# eNode_Spark.net
KiCad netlist of a schematic drawn in EAGLE
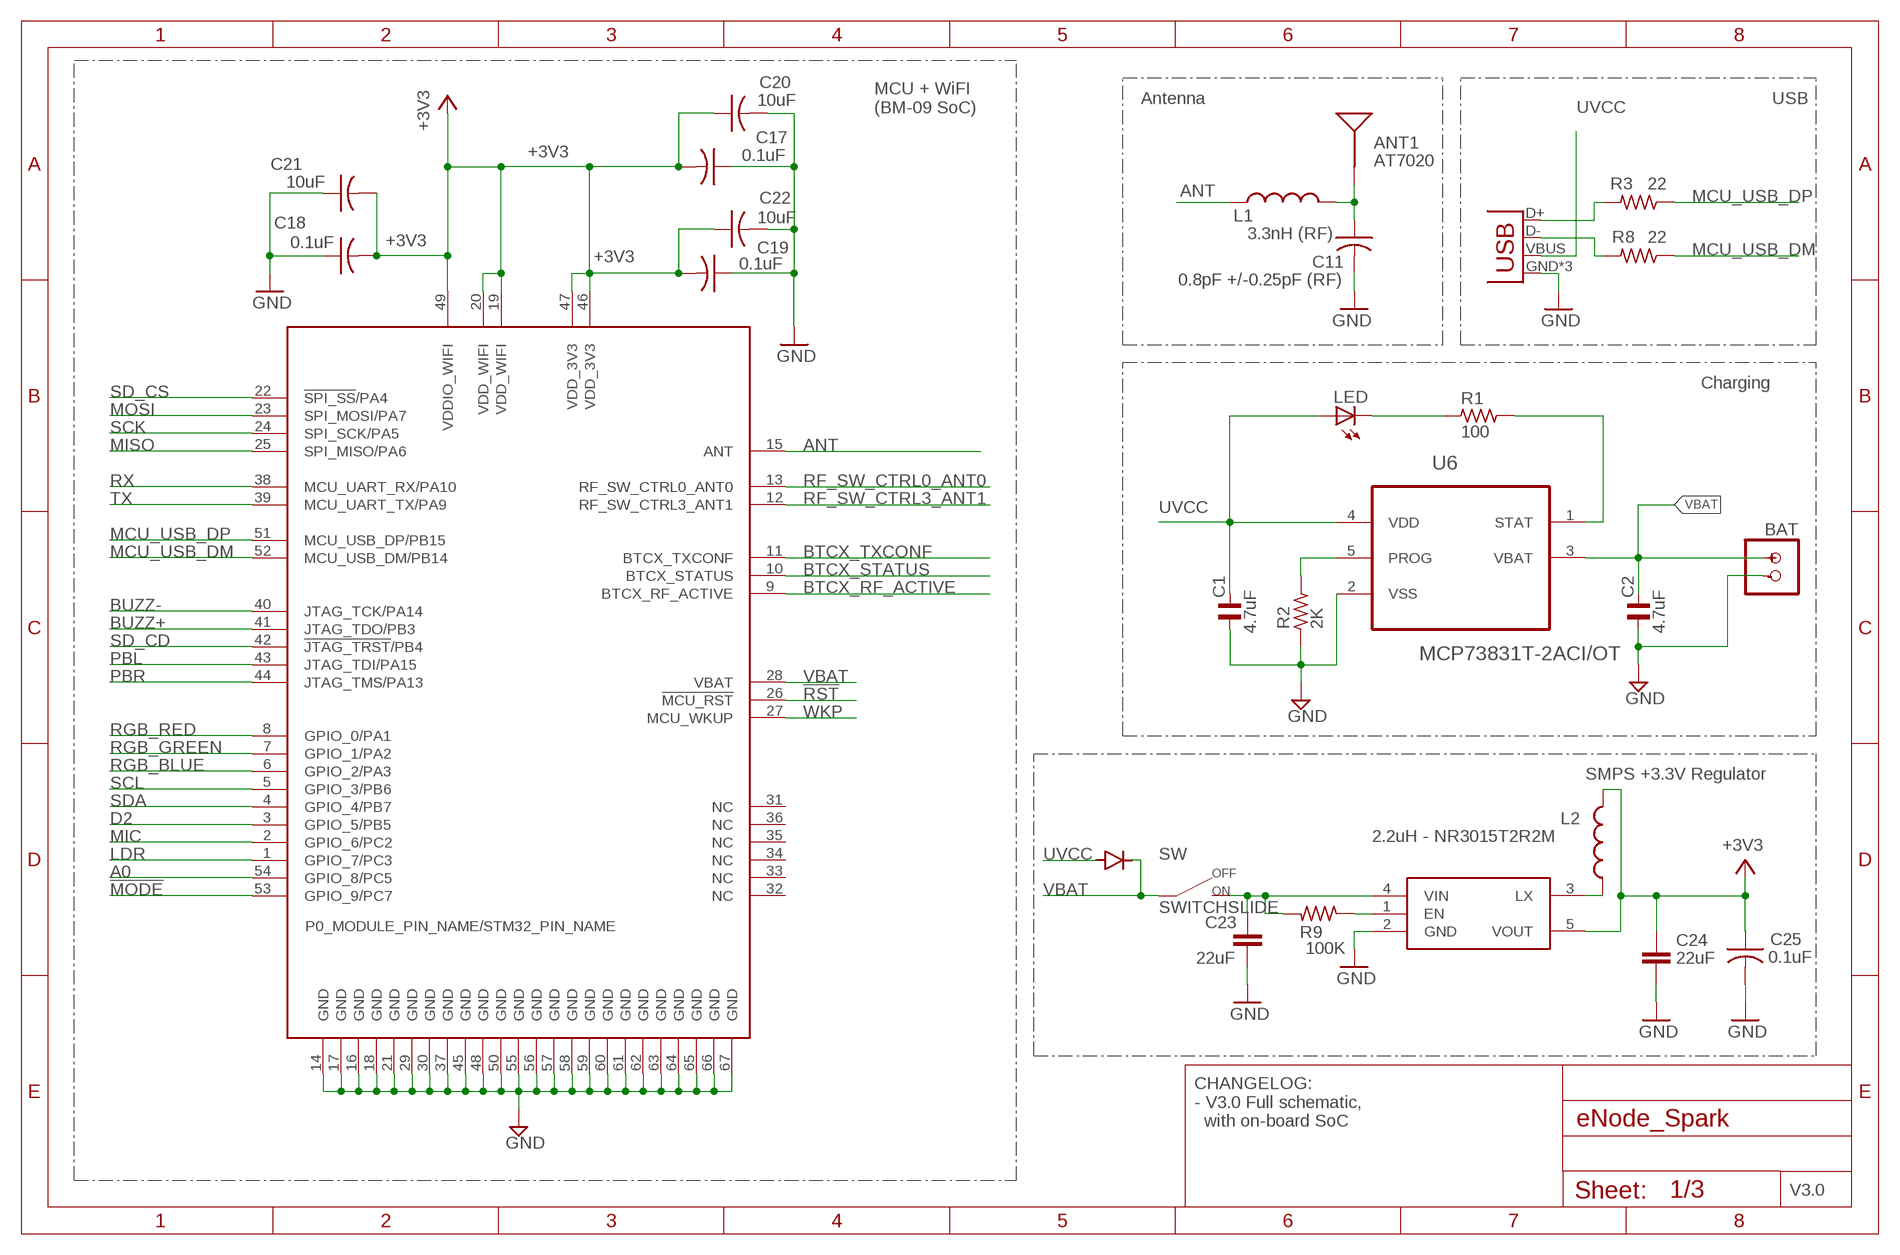
[diagram p0: schematic, sheet 1]
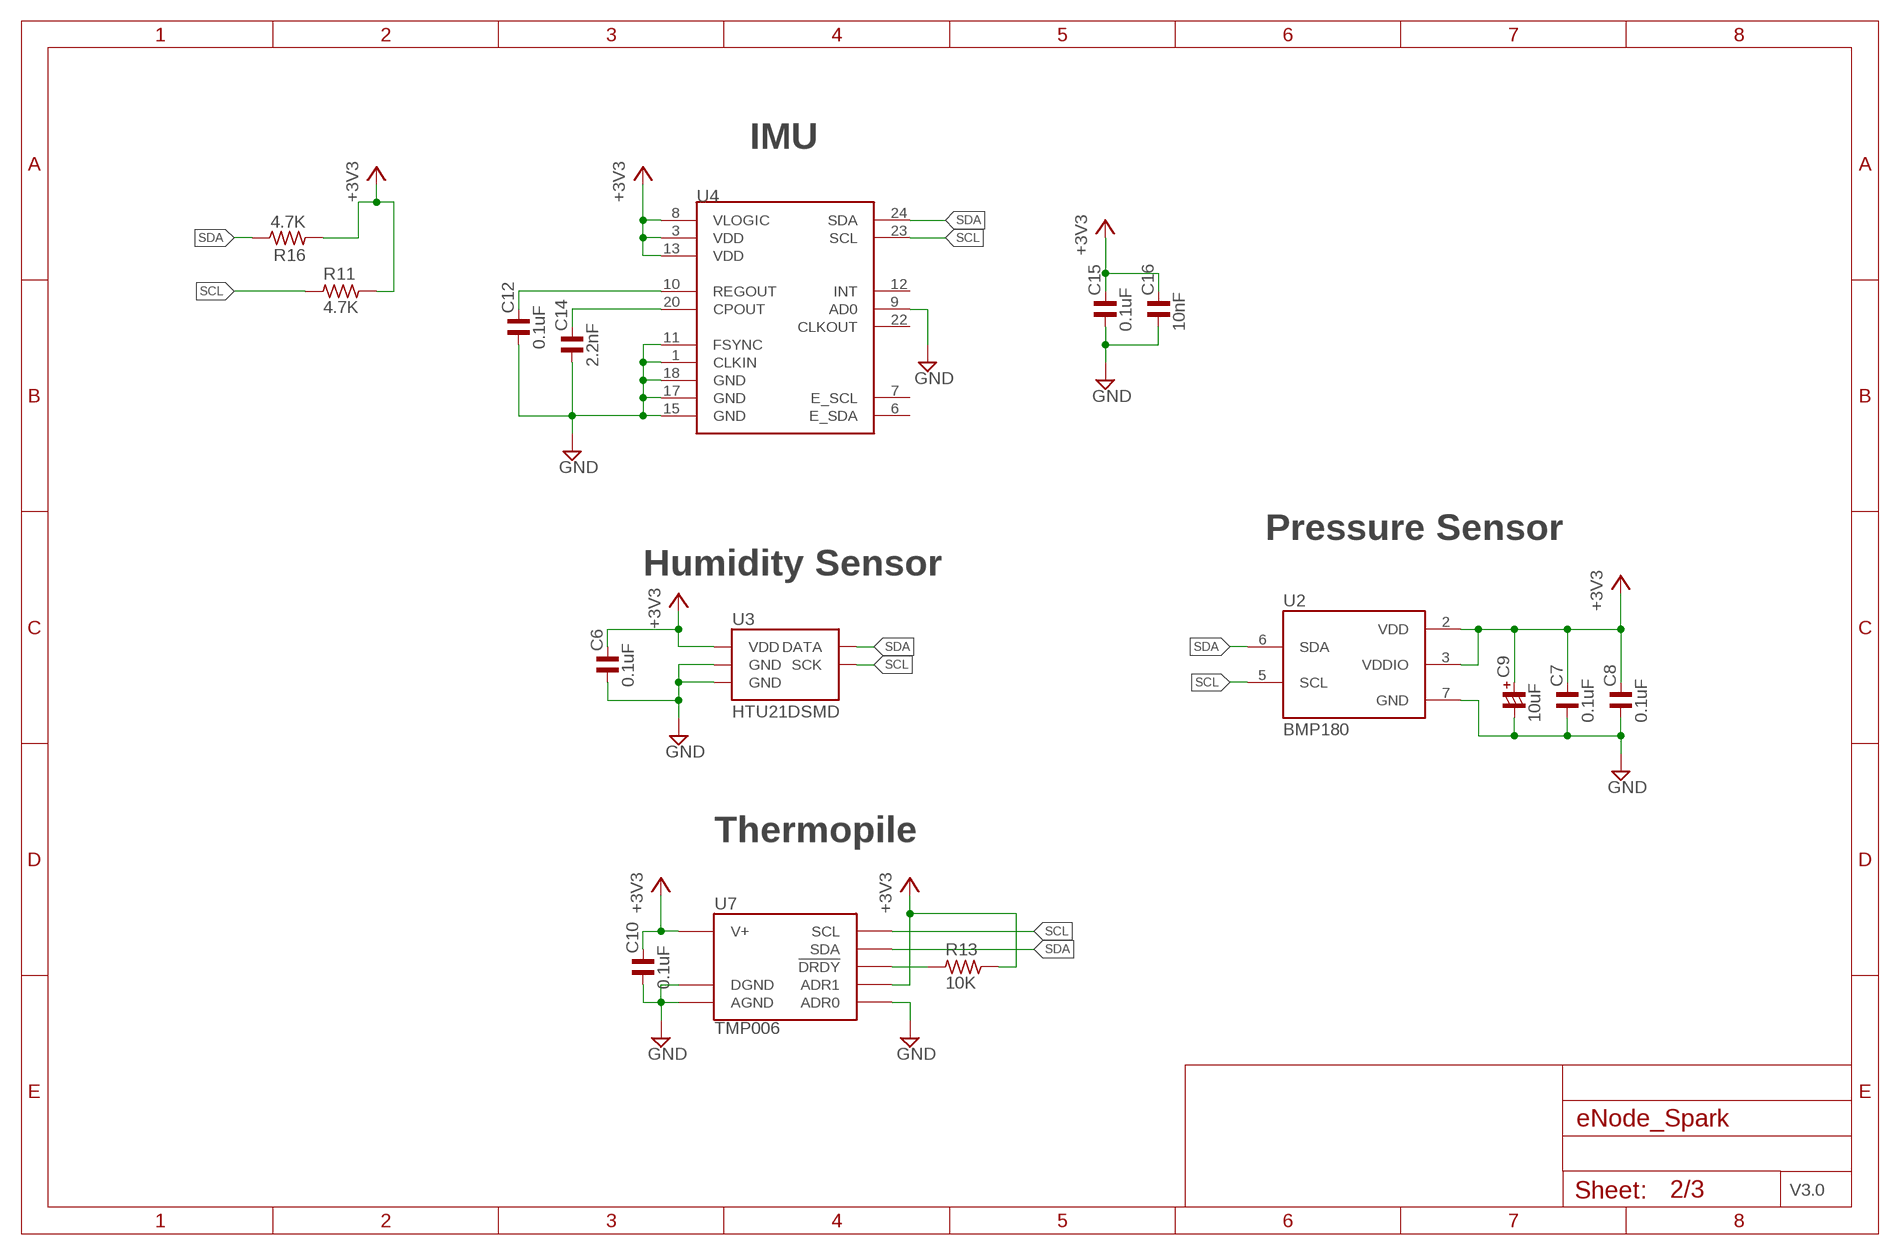
[diagram p1: schematic, sheet 2]
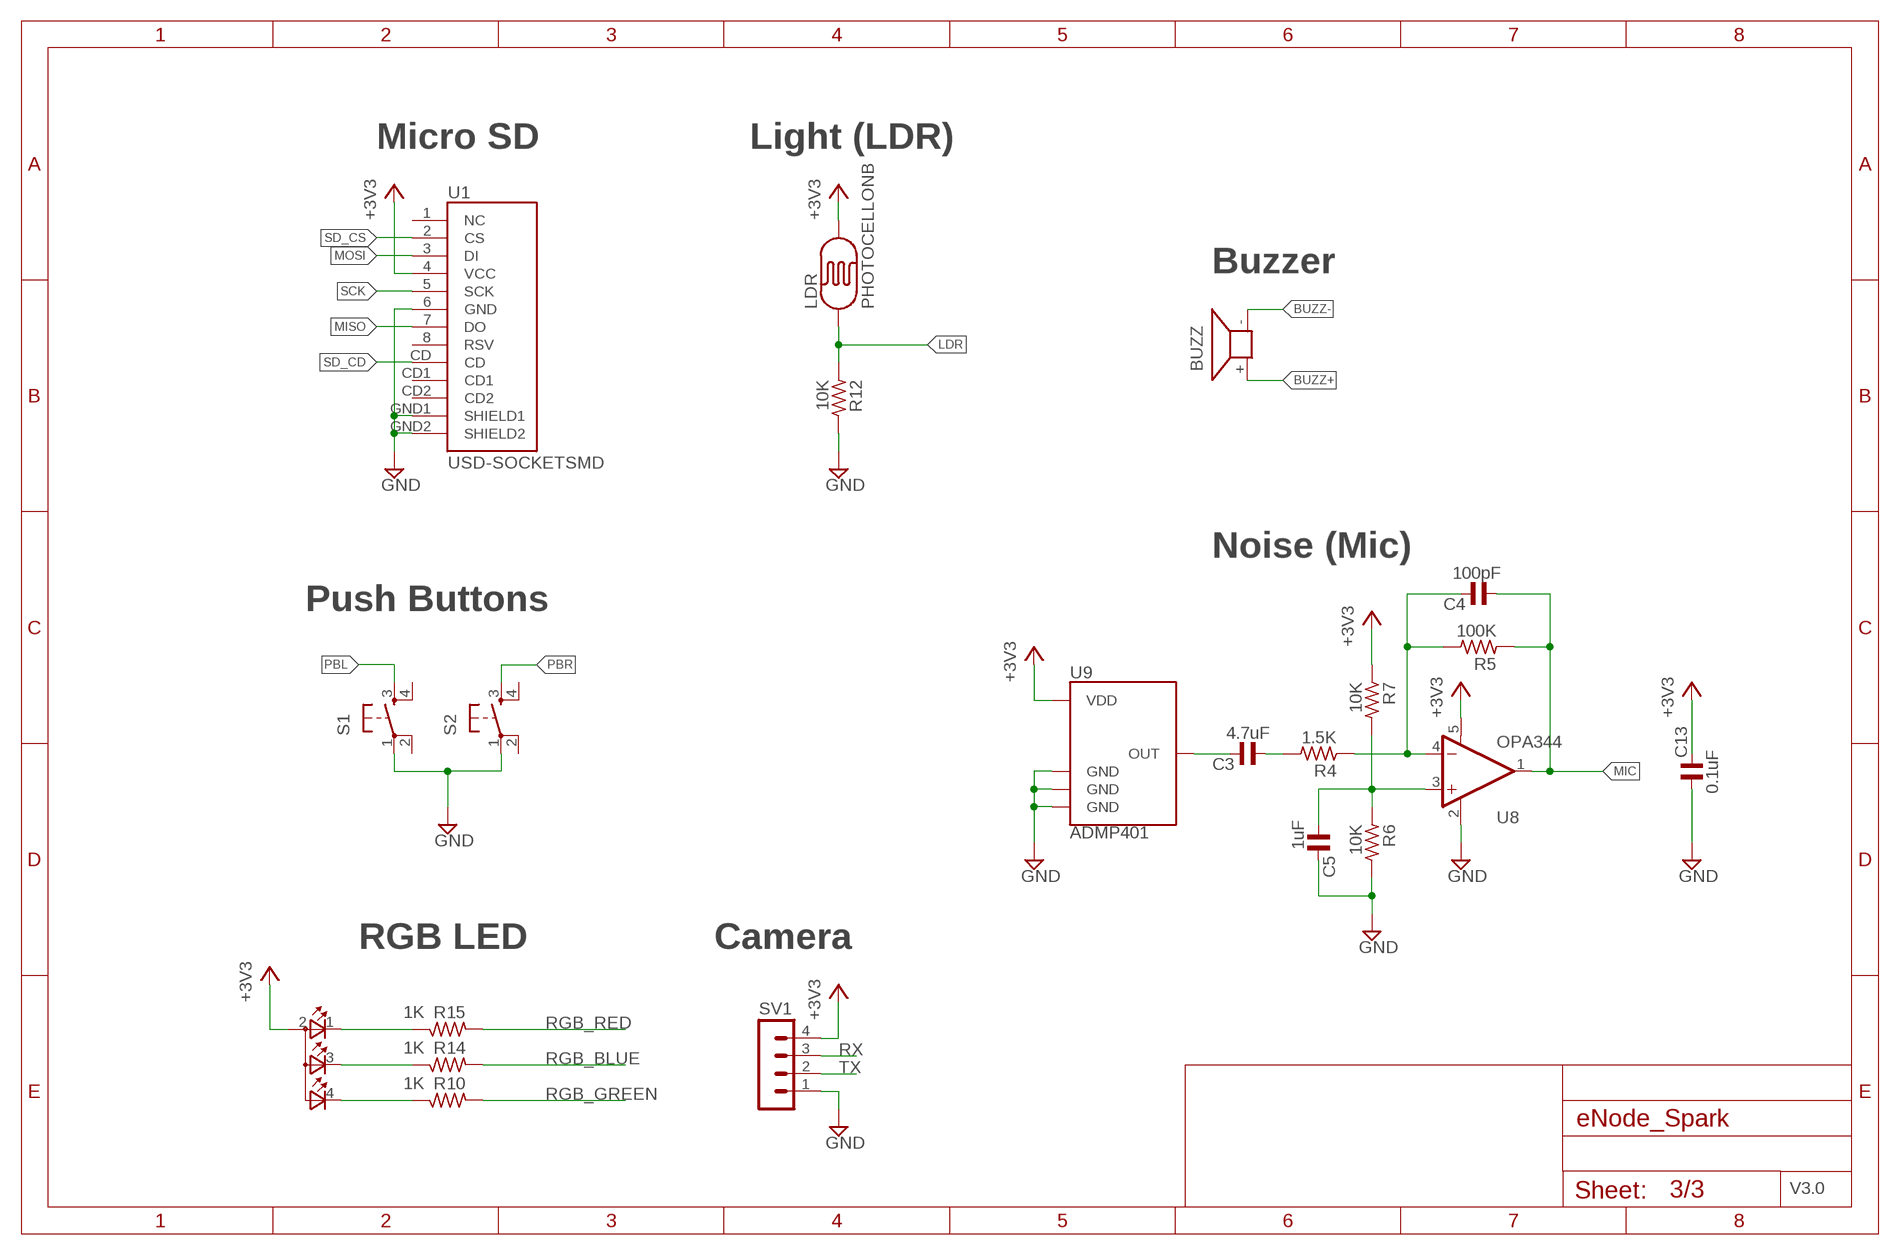
[diagram p2: schematic, sheet 3]

(export (version "E")
  (design (tool "Eeschema 10.0.6"))
  (components
    (comp (ref "C6")
      (value "0.1uF")
      (footprint "eagle-import:C0402")
      (libsource (lib "eagle-import") (part "C_0402"))
    )
    (comp (ref "C7")
      (value "0.1uF")
      (footprint "eagle-import:C0402")
      (libsource (lib "eagle-import") (part "C_0402"))
    )
    (comp (ref "C8")
      (value "0.1uF")
      (footprint "eagle-import:C0402")
      (libsource (lib "eagle-import") (part "C_0402"))
    )
    (comp (ref "C9")
      (value "10uF")
      (footprint "eagle-import:C1206_T")
      (libsource (lib "eagle-import") (part "CP_1206/T"))
    )
    (comp (ref "C10")
      (value "0.1uF")
      (footprint "eagle-import:C0402")
      (libsource (lib "eagle-import") (part "C_0402"))
    )
    (comp (ref "C12")
      (value "0.1uF")
      (footprint "eagle-import:C0402")
      (libsource (lib "eagle-import") (part "C_0402"))
    )
    (comp (ref "C14")
      (value "2.2nF")
      (footprint "eagle-import:C0402")
      (libsource (lib "eagle-import") (part "C_0402"))
    )
    (comp (ref "C15")
      (value "0.1uF")
      (footprint "eagle-import:C0402")
      (libsource (lib "eagle-import") (part "C_0402"))
    )
    (comp (ref "C16")
      (value "10nF")
      (footprint "eagle-import:C0402")
      (libsource (lib "eagle-import") (part "C_0402"))
    )
    (comp (ref "R11")
      (value "4.7K")
      (footprint "eagle-import:R0603")
      (libsource (lib "eagle-import") (part "R_0603"))
    )
    (comp (ref "R13")
      (value "10K")
      (footprint "eagle-import:R0603")
      (libsource (lib "eagle-import") (part "R_0603"))
    )
    (comp (ref "R16")
      (value "4.7K")
      (footprint "eagle-import:R0603")
      (libsource (lib "eagle-import") (part "R_0603"))
    )
    (comp (ref "U2")
      (value "BMP180")
      (footprint "eagle-import:BMP180")
      (libsource (lib "eagle-import") (part "BMP180"))
    )
    (comp (ref "U3")
      (value "HTU21DSMD")
      (footprint "eagle-import:HTU21D")
      (libsource (lib "eagle-import") (part "HTU21DSMD"))
    )
    (comp (ref "U4")
      (value "MPU-9150QFN-24-NP")
      (footprint "eagle-import:QFN-24-NP")
      (libsource (lib "eagle-import") (part "MPU-9150QFN-24-NP"))
    )
    (comp (ref "U7")
      (value "TMP006")
      (footprint "eagle-import:BGA8DS")
      (libsource (lib "eagle-import") (part "TMP006"))
    )
    (comp (ref "BUZZ")
      (value "BUZZER")
      (footprint "eagle-import:OFFBOARD_NOSIGN")
      (libsource (lib "eagle-import") (part "BUZZER"))
    )
    (comp (ref "C3")
      (value "4.7uF")
      (footprint "eagle-import:C0402")
      (libsource (lib "eagle-import") (part "C_0402"))
    )
    (comp (ref "C4")
      (value "100pF")
      (footprint "eagle-import:C0402")
      (libsource (lib "eagle-import") (part "C_0402"))
    )
    (comp (ref "C5")
      (value "1uF")
      (footprint "eagle-import:C0402")
      (libsource (lib "eagle-import") (part "C_0402"))
    )
    (comp (ref "C13")
      (value "0.1uF")
      (footprint "eagle-import:C0402")
      (libsource (lib "eagle-import") (part "C_0402"))
    )
    (comp (ref "LDR")
      (value "PHOTOCELLONB")
      (footprint "eagle-import:ON_BOARD")
      (libsource (lib "eagle-import") (part "PHOTOCELLONB"))
    )
    (comp (ref "LED2")
      (value "CREE_CLVBA-FKA")
      (footprint "eagle-import:P-LCC-4-3")
      (libsource (lib "eagle-import") (part "TOPLED-3PLCC"))
    )
    (comp (ref "R4")
      (value "1.5K")
      (footprint "eagle-import:R0402")
      (libsource (lib "eagle-import") (part "R_0402"))
    )
    (comp (ref "R5")
      (value "100K")
      (footprint "eagle-import:R0402")
      (libsource (lib "eagle-import") (part "R_0402"))
    )
    (comp (ref "R6")
      (value "10K")
      (footprint "eagle-import:R0402")
      (libsource (lib "eagle-import") (part "R_0402"))
    )
    (comp (ref "R7")
      (value "10K")
      (footprint "eagle-import:R0402")
      (libsource (lib "eagle-import") (part "R_0402"))
    )
    (comp (ref "R10")
      (value "1K")
      (footprint "eagle-import:R0402_B")
      (libsource (lib "eagle-import") (part "R-US_"))
    )
    (comp (ref "R12")
      (value "10K")
      (footprint "eagle-import:R0603")
      (libsource (lib "eagle-import") (part "R_0603"))
    )
    (comp (ref "R14")
      (value "1K")
      (footprint "eagle-import:R0402_B")
      (libsource (lib "eagle-import") (part "R-US_"))
    )
    (comp (ref "R15")
      (value "1K")
      (footprint "eagle-import:R0402_B")
      (libsource (lib "eagle-import") (part "R-US_"))
    )
    (comp (ref "S1")
      (value "TAC_SWITCHSMD")
      (footprint "eagle-import:TACTILE_SWITCH_SMD")
      (libsource (lib "eagle-import") (part "TAC_SWITCHSMD"))
    )
    (comp (ref "S2")
      (value "TAC_SWITCHSMD")
      (footprint "eagle-import:TACTILE_SWITCH_SMD")
      (libsource (lib "eagle-import") (part "TAC_SWITCHSMD"))
    )
    (comp (ref "SV1")
      (value "MA04-1")
      (footprint "eagle-import:MA04-1")
      (libsource (lib "eagle-import") (part "MA04-1"))
    )
    (comp (ref "U1")
      (value "USD-SOCKETSMD")
      (footprint "eagle-import:MICRO-SD-SOCKET-PP")
      (libsource (lib "eagle-import") (part "USD-SOCKETSMD"))
    )
    (comp (ref "U8")
      (value "OPA344")
      (footprint "eagle-import:SOT23-5")
      (libsource (lib "eagle-import") (part "OPA344"))
    )
    (comp (ref "U9")
      (value "ADMP401")
      (footprint "eagle-import:ADMP401")
      (libsource (lib "eagle-import") (part "ADMP401"))
    )
    (comp (ref "ANT1")
      (value "AT7020")
      (footprint "eagle-import:AT7020")
      (libsource (lib "eagle-import") (part "AT7020"))
    )
    (comp (ref "BAT")
      (value "BATTERYSMT")
      (footprint "eagle-import:JST-2-SMD")
      (libsource (lib "eagle-import") (part "BATTERYSMT"))
    )
    (comp (ref "C1")
      (value "4.7uF")
      (footprint "eagle-import:C0402")
      (libsource (lib "eagle-import") (part "C_0402"))
    )
    (comp (ref "C2")
      (value "4.7uF")
      (footprint "eagle-import:C0402")
      (libsource (lib "eagle-import") (part "C_0402"))
    )
    (comp (ref "C11")
      (value "0.8pF +/-0.25pF (RF)")
      (footprint "eagle-import:C0402_B")
      (libsource (lib "eagle-import") (part "C-US"))
    )
    (comp (ref "C17")
      (value "0.1uF")
      (footprint "eagle-import:C0402_B")
      (libsource (lib "eagle-import") (part "C-US"))
    )
    (comp (ref "C18")
      (value "0.1uF")
      (footprint "eagle-import:C0402_B")
      (libsource (lib "eagle-import") (part "C-US"))
    )
    (comp (ref "C19")
      (value "0.1uF")
      (footprint "eagle-import:C0402_B")
      (libsource (lib "eagle-import") (part "C-US"))
    )
    (comp (ref "C20")
      (value "10uF")
      (footprint "eagle-import:C0402_B")
      (libsource (lib "eagle-import") (part "C-US"))
    )
    (comp (ref "C21")
      (value "10uF")
      (footprint "eagle-import:C0402_B")
      (libsource (lib "eagle-import") (part "C-US"))
    )
    (comp (ref "C22")
      (value "10uF")
      (footprint "eagle-import:C0402_B")
      (libsource (lib "eagle-import") (part "C-US"))
    )
    (comp (ref "C23")
      (value "22uF")
      (footprint "eagle-import:C0603")
      (libsource (lib "eagle-import") (part "C-EUC0603"))
    )
    (comp (ref "C24")
      (value "22uF")
      (footprint "eagle-import:C0603")
      (libsource (lib "eagle-import") (part "C-EUC0603"))
    )
    (comp (ref "C25")
      (value "0.1uF")
      (footprint "eagle-import:C0402")
      (libsource (lib "eagle-import") (part "C-USC0402"))
    )
    (comp (ref "D1")
      (value "DIODE")
      (footprint "eagle-import:DIODE-DO-220AA(SMP)")
      (libsource (lib "eagle-import") (part "DIODE"))
    )
    (comp (ref "L1")
      (value "3.3nH (RF)")
      (footprint "eagle-import:L0402_B")
      (libsource (lib "eagle-import") (part "INDUCTOR"))
    )
    (comp (ref "L2")
      (value "2.2uH - NR3015T2R2M")
      (footprint "eagle-import:INDUCTOR-NR3015")
      (libsource (lib "eagle-import") (part "INDUCTORB"))
    )
    (comp (ref "LED")
      (value "LED")
      (footprint "eagle-import:RA_SMD_LED")
      (libsource (lib "eagle-import") (part "LED"))
    )
    (comp (ref "R1")
      (value "100")
      (footprint "eagle-import:R0603")
      (libsource (lib "eagle-import") (part "R_0603"))
    )
    (comp (ref "R2")
      (value "2K")
      (footprint "eagle-import:R0603")
      (libsource (lib "eagle-import") (part "R_0603"))
    )
    (comp (ref "R3")
      (value "22")
      (footprint "eagle-import:R0402_B")
      (libsource (lib "eagle-import") (part "R-US_"))
    )
    (comp (ref "R8")
      (value "22")
      (footprint "eagle-import:R0402_B")
      (libsource (lib "eagle-import") (part "R-US_"))
    )
    (comp (ref "R9")
      (value "100K")
      (footprint "eagle-import:R0402_B")
      (libsource (lib "eagle-import") (part "R-US_"))
    )
    (comp (ref "SW")
      (value "SWITCHSLIDE")
      (footprint "eagle-import:CHANGE_OVER_SLIDE")
      (libsource (lib "eagle-import") (part "SWITCHSLIDE"))
    )
    (comp (ref "U$7")
      (value "R8008-33")
      (footprint "eagle-import:SOT23-5")
      (libsource (lib "eagle-import") (part "R8008-33"))
    )
    (comp (ref "U6")
      (value "MCP73831T-2ACI/OT")
      (footprint "eagle-import:SOT95P280X145-5N")
      (libsource (lib "eagle-import") (part "MCP73831T-2ACI/OT"))
    )
    (comp (ref "U10")
      (value "WM-N-BM-09")
      (footprint "eagle-import:WM-N-BM-09")
      (libsource (lib "eagle-import") (part "WM-N-BM-09"))
    )
    (comp (ref "X1")
      (value "USB-MICROB")
      (footprint "eagle-import:USB-MICROB-SLOT-HOLE")
      (libsource (lib "eagle-import") (part "USBUSB-MICROB-SLOT-HOLE"))
    )
  )
  (nets
    (net (code "1") (name "+3V3") (class "Default")
      (node (ref "C10") (pin "2") (pinfunction "2_2") (pintype "passive"))
      (node (ref "C13") (pin "2") (pinfunction "2_2") (pintype "passive"))
      (node (ref "C15") (pin "2") (pinfunction "2_2") (pintype "passive"))
      (node (ref "C16") (pin "2") (pinfunction "2_2") (pintype "passive"))
      (node (ref "C17") (pin "2") (pinfunction "2_2") (pintype "passive"))
      (node (ref "C18") (pin "2") (pinfunction "2_2") (pintype "passive"))
      (node (ref "C19") (pin "2") (pinfunction "2_2") (pintype "passive"))
      (node (ref "C20") (pin "1") (pinfunction "1_1") (pintype "passive"))
      (node (ref "C21") (pin "2") (pinfunction "2_2") (pintype "passive"))
      (node (ref "C22") (pin "1") (pinfunction "1_1") (pintype "passive"))
      (node (ref "C24") (pin "1") (pinfunction "1_1") (pintype "passive"))
      (node (ref "C25") (pin "1") (pinfunction "1_1") (pintype "passive"))
      (node (ref "C6") (pin "2") (pinfunction "2_2") (pintype "passive"))
      (node (ref "C7") (pin "2") (pinfunction "2_2") (pintype "passive"))
      (node (ref "C8") (pin "2") (pinfunction "2_2") (pintype "passive"))
      (node (ref "C9") (pin "+") (pinfunction "+_+") (pintype "passive"))
      (node (ref "L2") (pin "2") (pinfunction "2_2") (pintype "passive"))
      (node (ref "LDR") (pin "2") (pinfunction "P$2_2") (pintype "bidirectional"))
      (node (ref "LED2") (pin "2") (pinfunction "A2_2") (pintype "passive"))
      (node (ref "R11") (pin "2") (pinfunction "2_2") (pintype "passive"))
      (node (ref "R13") (pin "2") (pinfunction "2_2") (pintype "passive"))
      (node (ref "R16") (pin "1") (pinfunction "1_1") (pintype "passive"))
      (node (ref "R7") (pin "1") (pinfunction "1_1") (pintype "passive"))
      (node (ref "SV1") (pin "4") (pinfunction "4_4") (pintype "passive"))
      (node (ref "U$7") (pin "5") (pinfunction "VOUT_5") (pintype "bidirectional"))
      (node (ref "U1") (pin "4") (pinfunction "VCC_4") (pintype "bidirectional"))
      (node (ref "U10") (pin "19") (pinfunction "VDD_WIFI_19") (pintype "bidirectional"))
      (node (ref "U10") (pin "20") (pinfunction "VDD_WIFI_20") (pintype "bidirectional"))
      (node (ref "U10") (pin "46") (pinfunction "VDD_3V3_46") (pintype "bidirectional"))
      (node (ref "U10") (pin "47") (pinfunction "VDD_3V3_47") (pintype "bidirectional"))
      (node (ref "U10") (pin "49") (pinfunction "VDDIO_WIFI_49") (pintype "bidirectional"))
      (node (ref "U2") (pin "2") (pinfunction "VDD_2") (pintype "power_in"))
      (node (ref "U2") (pin "3") (pinfunction "VDDIO_3") (pintype "power_in"))
      (node (ref "U3") (pin "VDD") (pinfunction "VDD_VDD") (pintype "power_in"))
      (node (ref "U4") (pin "13") (pinfunction "VDD_13") (pintype "bidirectional"))
      (node (ref "U4") (pin "3") (pinfunction "VDD_3") (pintype "bidirectional"))
      (node (ref "U4") (pin "8") (pinfunction "VLOGIC_8") (pintype "bidirectional"))
      (node (ref "U7") (pin "A3") (pinfunction "V+_A3") (pintype "bidirectional"))
      (node (ref "U7") (pin "B1") (pinfunction "ADR1_B1") (pintype "bidirectional"))
      (node (ref "U8") (pin "5") (pinfunction "V+_5") (pintype "power_in"))
      (node (ref "U9") (pin "5") (pinfunction "VDD_5") (pintype "bidirectional"))
    )
    (net (code "2") (name "A0") (class "Default")
      (node (ref "U10") (pin "54") (pinfunction "GPIO_8/PC5_54") (pintype "bidirectional"))
    )
    (net (code "3") (name "ANT") (class "Default")
      (node (ref "L1") (pin "1") (pinfunction "1_1") (pintype "passive"))
      (node (ref "U10") (pin "15") (pinfunction "ANT_15") (pintype "bidirectional"))
    )
    (net (code "4") (name "BTCX_RF_ACTIVE") (class "Default")
      (node (ref "U10") (pin "9") (pinfunction "BTCX_RF_ACTIVE_9") (pintype "bidirectional"))
    )
    (net (code "5") (name "BTCX_STATUS") (class "Default")
      (node (ref "U10") (pin "10") (pinfunction "BTCX_STATUS_10") (pintype "bidirectional"))
    )
    (net (code "6") (name "BTCX_TXCONF") (class "Default")
      (node (ref "U10") (pin "11") (pinfunction "BTCX_TXCONF_11") (pintype "bidirectional"))
    )
    (net (code "7") (name "BUZZ+") (class "Default")
      (node (ref "BUZZ") (pin "+") (pinfunction "+_+") (pintype "passive"))
      (node (ref "U10") (pin "41") (pinfunction "JTAG_TDO/PB3_41") (pintype "bidirectional"))
    )
    (net (code "8") (name "BUZZ-") (class "Default")
      (node (ref "BUZZ") (pin "-") (pinfunction "-_-") (pintype "passive"))
      (node (ref "U10") (pin "40") (pinfunction "JTAG_TCK/PA14_40") (pintype "bidirectional"))
    )
    (net (code "9") (name "D2") (class "Default")
      (node (ref "U10") (pin "3") (pinfunction "GPIO_5/PB5_3") (pintype "bidirectional"))
    )
    (net (code "10") (name "GND") (class "Default")
      (node (ref "BAT") (pin "-") (pinfunction "-_-") (pintype "passive"))
      (node (ref "C1") (pin "1") (pinfunction "1_1") (pintype "passive"))
      (node (ref "C10") (pin "1") (pinfunction "1_1") (pintype "passive"))
      (node (ref "C11") (pin "2") (pinfunction "2_2") (pintype "passive"))
      (node (ref "C12") (pin "1") (pinfunction "1_1") (pintype "passive"))
      (node (ref "C13") (pin "1") (pinfunction "1_1") (pintype "passive"))
      (node (ref "C14") (pin "1") (pinfunction "1_1") (pintype "passive"))
      (node (ref "C15") (pin "1") (pinfunction "1_1") (pintype "passive"))
      (node (ref "C16") (pin "1") (pinfunction "1_1") (pintype "passive"))
      (node (ref "C17") (pin "1") (pinfunction "1_1") (pintype "passive"))
      (node (ref "C18") (pin "1") (pinfunction "1_1") (pintype "passive"))
      (node (ref "C19") (pin "1") (pinfunction "1_1") (pintype "passive"))
      (node (ref "C2") (pin "1") (pinfunction "1_1") (pintype "passive"))
      (node (ref "C20") (pin "2") (pinfunction "2_2") (pintype "passive"))
      (node (ref "C21") (pin "1") (pinfunction "1_1") (pintype "passive"))
      (node (ref "C22") (pin "2") (pinfunction "2_2") (pintype "passive"))
      (node (ref "C23") (pin "2") (pinfunction "2_2") (pintype "passive"))
      (node (ref "C24") (pin "2") (pinfunction "2_2") (pintype "passive"))
      (node (ref "C25") (pin "2") (pinfunction "2_2") (pintype "passive"))
      (node (ref "C5") (pin "2") (pinfunction "2_2") (pintype "passive"))
      (node (ref "C6") (pin "1") (pinfunction "1_1") (pintype "passive"))
      (node (ref "C7") (pin "1") (pinfunction "1_1") (pintype "passive"))
      (node (ref "C8") (pin "1") (pinfunction "1_1") (pintype "passive"))
      (node (ref "C9") (pin "-") (pinfunction "-_-") (pintype "passive"))
      (node (ref "R12") (pin "2") (pinfunction "2_2") (pintype "passive"))
      (node (ref "R2") (pin "1") (pinfunction "1_1") (pintype "passive"))
      (node (ref "R6") (pin "2") (pinfunction "2_2") (pintype "passive"))
      (node (ref "S1") (pin "1") (pinfunction "1_1") (pintype "passive"))
      (node (ref "S2") (pin "1") (pinfunction "1_1") (pintype "passive"))
      (node (ref "SV1") (pin "1") (pinfunction "1_1") (pintype "passive"))
      (node (ref "U$7") (pin "2") (pinfunction "GND_2") (pintype "bidirectional"))
      (node (ref "U1") (pin "6") (pinfunction "GND_6") (pintype "bidirectional"))
      (node (ref "U1") (pin "GND1") (pinfunction "SHIELD1_GND1") (pintype "bidirectional"))
      (node (ref "U1") (pin "GND2") (pinfunction "SHIELD2_GND2") (pintype "bidirectional"))
      (node (ref "U10") (pin "14") (pinfunction "GND_14") (pintype "bidirectional"))
      (node (ref "U10") (pin "16") (pinfunction "GND_16") (pintype "bidirectional"))
      (node (ref "U10") (pin "17") (pinfunction "GND_17") (pintype "bidirectional"))
      (node (ref "U10") (pin "18") (pinfunction "GND_18") (pintype "bidirectional"))
      (node (ref "U10") (pin "21") (pinfunction "GND_21") (pintype "bidirectional"))
      (node (ref "U10") (pin "29") (pinfunction "GND_29") (pintype "bidirectional"))
      (node (ref "U10") (pin "30") (pinfunction "GND_30") (pintype "bidirectional"))
      (node (ref "U10") (pin "37") (pinfunction "GND_37") (pintype "bidirectional"))
      (node (ref "U10") (pin "45") (pinfunction "GND_45") (pintype "bidirectional"))
      (node (ref "U10") (pin "48") (pinfunction "GND_48") (pintype "bidirectional"))
      (node (ref "U10") (pin "50") (pinfunction "GND_50") (pintype "bidirectional"))
      (node (ref "U10") (pin "55") (pinfunction "GND_55") (pintype "bidirectional"))
      (node (ref "U10") (pin "56") (pinfunction "GND_56") (pintype "bidirectional"))
      (node (ref "U10") (pin "57") (pinfunction "GND_57") (pintype "bidirectional"))
      (node (ref "U10") (pin "58") (pinfunction "GND_58") (pintype "bidirectional"))
      (node (ref "U10") (pin "59") (pinfunction "GND_59") (pintype "bidirectional"))
      (node (ref "U10") (pin "60") (pinfunction "GND_60") (pintype "bidirectional"))
      (node (ref "U10") (pin "61") (pinfunction "GND_61") (pintype "bidirectional"))
      (node (ref "U10") (pin "62") (pinfunction "GND_62") (pintype "bidirectional"))
      (node (ref "U10") (pin "63") (pinfunction "GND_63") (pintype "bidirectional"))
      (node (ref "U10") (pin "64") (pinfunction "GND_64") (pintype "bidirectional"))
      (node (ref "U10") (pin "65") (pinfunction "GND_65") (pintype "bidirectional"))
      (node (ref "U10") (pin "66") (pinfunction "GND_66") (pintype "bidirectional"))
      (node (ref "U10") (pin "67") (pinfunction "GND_67") (pintype "bidirectional"))
      (node (ref "U2") (pin "7") (pinfunction "GND_7") (pintype "power_in"))
      (node (ref "U3") (pin "7") (pinfunction "GND_7") (pintype "power_in"))
      (node (ref "U3") (pin "GND") (pinfunction "GND_GND") (pintype "power_in"))
      (node (ref "U4") (pin "1") (pinfunction "CLKIN_1") (pintype "bidirectional"))
      (node (ref "U4") (pin "11") (pinfunction "FSYNC_11") (pintype "bidirectional"))
      (node (ref "U4") (pin "15") (pinfunction "GND_15") (pintype "bidirectional"))
      (node (ref "U4") (pin "17") (pinfunction "GND_17") (pintype "bidirectional"))
      (node (ref "U4") (pin "18") (pinfunction "GND_18") (pintype "bidirectional"))
      (node (ref "U4") (pin "9") (pinfunction "AD0_9") (pintype "bidirectional"))
      (node (ref "U6") (pin "2") (pinfunction "VSS_2") (pintype "power_in"))
      (node (ref "U7") (pin "A1") (pinfunction "DGND_A1") (pintype "bidirectional"))
      (node (ref "U7") (pin "A2") (pinfunction "AGND_A2") (pintype "bidirectional"))
      (node (ref "U7") (pin "C1") (pinfunction "ADR0_C1") (pintype "bidirectional"))
      (node (ref "U8") (pin "2") (pinfunction "V-_2") (pintype "power_in"))
      (node (ref "U9") (pin "2") (pinfunction "GND_2") (pintype "bidirectional"))
      (node (ref "U9") (pin "4") (pinfunction "GND_4") (pintype "bidirectional"))
      (node (ref "U9") (pin "6") (pinfunction "GND_6") (pintype "bidirectional"))
      (node (ref "X1") (pin "GND") (pinfunction "GND_GND") (pintype "bidirectional"))
      (node (ref "X1") (pin "MT1") (pinfunction "GND_MT1") (pintype "bidirectional"))
      (node (ref "X1") (pin "MT2") (pinfunction "GND_MT2") (pintype "bidirectional"))
    )
    (net (code "11") (name "LDR") (class "Default")
      (node (ref "LDR") (pin "1") (pinfunction "P$1_1") (pintype "bidirectional"))
      (node (ref "R12") (pin "1") (pinfunction "1_1") (pintype "passive"))
      (node (ref "U10") (pin "1") (pinfunction "GPIO_7/PC3_1") (pintype "bidirectional"))
    )
    (net (code "12") (name "MCU_USB_DM") (class "Default")
      (node (ref "R8") (pin "1") (pinfunction "1_1") (pintype "passive"))
      (node (ref "U10") (pin "52") (pinfunction "MCU_USB_DM/PB14_52") (pintype "bidirectional"))
    )
    (net (code "13") (name "MCU_USB_DP") (class "Default")
      (node (ref "R3") (pin "1") (pinfunction "1_1") (pintype "passive"))
      (node (ref "U10") (pin "51") (pinfunction "MCU_USB_DP/PB15_51") (pintype "bidirectional"))
    )
    (net (code "14") (name "MIC") (class "Default")
      (node (ref "C4") (pin "1") (pinfunction "1_1") (pintype "passive"))
      (node (ref "R5") (pin "1") (pinfunction "1_1") (pintype "passive"))
      (node (ref "U10") (pin "2") (pinfunction "GPIO_6/PC2_2") (pintype "bidirectional"))
      (node (ref "U8") (pin "1") (pinfunction "OUT_1") (pintype "output"))
    )
    (net (code "15") (name "MISO") (class "Default")
      (node (ref "U1") (pin "7") (pinfunction "DO_7") (pintype "bidirectional"))
      (node (ref "U10") (pin "25") (pinfunction "SPI_MISO/PA6_25") (pintype "bidirectional"))
    )
    (net (code "16") (name "MOSI") (class "Default")
      (node (ref "U1") (pin "3") (pinfunction "DI_3") (pintype "bidirectional"))
      (node (ref "U10") (pin "23") (pinfunction "SPI_MOSI/PA7_23") (pintype "bidirectional"))
    )
    (net (code "17") (name "Net-(ANT1-SIGNAL)") (class "Default")
      (node (ref "ANT1") (pin "1") (pinfunction "SIGNAL_1") (pintype "bidirectional"))
      (node (ref "C11") (pin "1") (pinfunction "1_1") (pintype "passive"))
      (node (ref "L1") (pin "2") (pinfunction "2_2") (pintype "passive"))
    )
    (net (code "18") (name "Net-(C3-Pad1)") (class "Default")
      (node (ref "C3") (pin "1") (pinfunction "1_1") (pintype "passive"))
      (node (ref "R4") (pin "2") (pinfunction "2_2") (pintype "passive"))
    )
    (net (code "19") (name "Net-(LED-PadC)") (class "Default")
      (node (ref "LED") (pin "C") (pinfunction "C_C") (pintype "passive"))
      (node (ref "R1") (pin "1") (pinfunction "1_1") (pintype "passive"))
    )
    (net (code "20") (name "Net-(LED2-CBLUE)") (class "Default")
      (node (ref "LED2") (pin "3") (pinfunction "CBLUE_3") (pintype "passive"))
      (node (ref "R14") (pin "1") (pinfunction "1_1") (pintype "passive"))
    )
    (net (code "21") (name "Net-(LED2-CGREEN)") (class "Default")
      (node (ref "LED2") (pin "4") (pinfunction "CGREEN_4") (pintype "passive"))
      (node (ref "R10") (pin "1") (pinfunction "1_1") (pintype "passive"))
    )
    (net (code "22") (name "Net-(LED2-CRED)") (class "Default")
      (node (ref "LED2") (pin "1") (pinfunction "CRED_1") (pintype "passive"))
      (node (ref "R15") (pin "1") (pinfunction "1_1") (pintype "passive"))
    )
    (net (code "23") (name "Net-(R3-Pad2)") (class "Default")
      (node (ref "R3") (pin "2") (pinfunction "2_2") (pintype "passive"))
      (node (ref "X1") (pin "D+") (pinfunction "D+_D+") (pintype "bidirectional"))
    )
    (net (code "24") (name "Net-(R8-Pad2)") (class "Default")
      (node (ref "R8") (pin "2") (pinfunction "2_2") (pintype "passive"))
      (node (ref "X1") (pin "D-") (pinfunction "D-_D-") (pintype "bidirectional"))
    )
    (net (code "25") (name "Net-(U$7-EN)") (class "Default")
      (node (ref "R9") (pin "1") (pinfunction "1_1") (pintype "passive"))
      (node (ref "U$7") (pin "1") (pinfunction "EN_1") (pintype "bidirectional"))
    )
    (net (code "26") (name "Net-(U$7-LX)") (class "Default")
      (node (ref "L2") (pin "1") (pinfunction "1_1") (pintype "passive"))
      (node (ref "U$7") (pin "3") (pinfunction "LX_3") (pintype "bidirectional"))
    )
    (net (code "27") (name "Net-(U4-CPOUT)") (class "Default")
      (node (ref "C14") (pin "2") (pinfunction "2_2") (pintype "passive"))
      (node (ref "U4") (pin "20") (pinfunction "CPOUT_20") (pintype "bidirectional"))
    )
    (net (code "28") (name "Net-(U4-REGOUT)") (class "Default")
      (node (ref "C12") (pin "2") (pinfunction "2_2") (pintype "passive"))
      (node (ref "U4") (pin "10") (pinfunction "REGOUT_10") (pintype "bidirectional"))
    )
    (net (code "29") (name "Net-(U6-PROG)") (class "Default")
      (node (ref "R2") (pin "2") (pinfunction "2_2") (pintype "passive"))
      (node (ref "U6") (pin "5") (pinfunction "PROG_5") (pintype "input"))
    )
    (net (code "30") (name "Net-(U6-STAT)") (class "Default")
      (node (ref "R1") (pin "2") (pinfunction "2_2") (pintype "passive"))
      (node (ref "U6") (pin "1") (pinfunction "STAT_1") (pintype "output"))
    )
    (net (code "31") (name "Net-(U7-~{DRDY})") (class "Default")
      (node (ref "R13") (pin "1") (pinfunction "1_1") (pintype "passive"))
      (node (ref "U7") (pin "C2") (pinfunction "~{DRDY}_C2") (pintype "bidirectional"))
    )
    (net (code "32") (name "Net-(U8-+IN)") (class "Default")
      (node (ref "C5") (pin "1") (pinfunction "1_1") (pintype "passive"))
      (node (ref "R6") (pin "1") (pinfunction "1_1") (pintype "passive"))
      (node (ref "R7") (pin "2") (pinfunction "2_2") (pintype "passive"))
      (node (ref "U8") (pin "3") (pinfunction "+IN_3") (pintype "input"))
    )
    (net (code "33") (name "Net-(U8--IN)") (class "Default")
      (node (ref "C4") (pin "2") (pinfunction "2_2") (pintype "passive"))
      (node (ref "R4") (pin "1") (pinfunction "1_1") (pintype "passive"))
      (node (ref "R5") (pin "2") (pinfunction "2_2") (pintype "passive"))
      (node (ref "U8") (pin "4") (pinfunction "-IN_4") (pintype "input"))
    )
    (net (code "34") (name "Net-(U9-OUT)") (class "Default")
      (node (ref "C3") (pin "2") (pinfunction "2_2") (pintype "passive"))
      (node (ref "U9") (pin "1") (pinfunction "OUT_1") (pintype "bidirectional"))
    )
    (net (code "35") (name "PBL") (class "Default")
      (node (ref "S1") (pin "3") (pinfunction "3_3") (pintype "passive"))
      (node (ref "U10") (pin "43") (pinfunction "JTAG_TDI/PA15_43") (pintype "bidirectional"))
    )
    (net (code "36") (name "PBR") (class "Default")
      (node (ref "S2") (pin "3") (pinfunction "3_3") (pintype "passive"))
      (node (ref "U10") (pin "44") (pinfunction "JTAG_TMS/PA13_44") (pintype "bidirectional"))
    )
    (net (code "37") (name "RF_SW_CTRL0_ANT0") (class "Default")
      (node (ref "U10") (pin "13") (pinfunction "RF_SW_CTRL0_ANT0_13") (pintype "bidirectional"))
    )
    (net (code "38") (name "RF_SW_CTRL3_ANT1") (class "Default")
      (node (ref "U10") (pin "12") (pinfunction "RF_SW_CTRL3_ANT1_12") (pintype "bidirectional"))
    )
    (net (code "39") (name "RGB_BLUE") (class "Default")
      (node (ref "R14") (pin "2") (pinfunction "2_2") (pintype "passive"))
      (node (ref "U10") (pin "6") (pinfunction "GPIO_2/PA3_6") (pintype "bidirectional"))
    )
    (net (code "40") (name "RGB_GREEN") (class "Default")
      (node (ref "R10") (pin "2") (pinfunction "2_2") (pintype "passive"))
      (node (ref "U10") (pin "7") (pinfunction "GPIO_1/PA2_7") (pintype "bidirectional"))
    )
    (net (code "41") (name "RGB_RED") (class "Default")
      (node (ref "R15") (pin "2") (pinfunction "2_2") (pintype "passive"))
      (node (ref "U10") (pin "8") (pinfunction "GPIO_0/PA1_8") (pintype "bidirectional"))
    )
    (net (code "42") (name "RX") (class "Default")
      (node (ref "SV1") (pin "3") (pinfunction "3_3") (pintype "passive"))
      (node (ref "U10") (pin "38") (pinfunction "MCU_UART_RX/PA10_38") (pintype "bidirectional"))
    )
    (net (code "43") (name "SCK") (class "Default")
      (node (ref "U1") (pin "5") (pinfunction "SCK_5") (pintype "bidirectional"))
      (node (ref "U10") (pin "24") (pinfunction "SPI_SCK/PA5_24") (pintype "bidirectional"))
    )
    (net (code "44") (name "SCL") (class "Default")
      (node (ref "R11") (pin "1") (pinfunction "1_1") (pintype "passive"))
      (node (ref "U10") (pin "5") (pinfunction "GPIO_3/PB6_5") (pintype "bidirectional"))
      (node (ref "U2") (pin "5") (pinfunction "SCL_5") (pintype "input"))
      (node (ref "U3") (pin "SCK") (pinfunction "SCK_SCK") (pintype "input"))
      (node (ref "U4") (pin "23") (pinfunction "SCL_23") (pintype "bidirectional"))
      (node (ref "U7") (pin "B3") (pinfunction "SCL_B3") (pintype "bidirectional"))
    )
    (net (code "45") (name "SDA") (class "Default")
      (node (ref "R16") (pin "2") (pinfunction "2_2") (pintype "passive"))
      (node (ref "U10") (pin "4") (pinfunction "GPIO_4/PB7_4") (pintype "bidirectional"))
      (node (ref "U2") (pin "6") (pinfunction "SDA_6") (pintype "bidirectional"))
      (node (ref "U3") (pin "DATA") (pinfunction "DATA_DATA") (pintype "bidirectional"))
      (node (ref "U4") (pin "24") (pinfunction "SDA_24") (pintype "bidirectional"))
      (node (ref "U7") (pin "C3") (pinfunction "SDA_C3") (pintype "bidirectional"))
    )
    (net (code "46") (name "SD_CD") (class "Default")
      (node (ref "U1") (pin "CD") (pinfunction "CD_CD") (pintype "bidirectional"))
      (node (ref "U10") (pin "42") (pinfunction "~{JTAG_TRST}/PB4_42") (pintype "bidirectional"))
    )
    (net (code "47") (name "SD_CS") (class "Default")
      (node (ref "U1") (pin "2") (pinfunction "CS_2") (pintype "bidirectional"))
      (node (ref "U10") (pin "22") (pinfunction "~{SPI_SS}/PA4_22") (pintype "bidirectional"))
    )
    (net (code "48") (name "TX") (class "Default")
      (node (ref "SV1") (pin "2") (pinfunction "2_2") (pintype "passive"))
      (node (ref "U10") (pin "39") (pinfunction "MCU_UART_TX/PA9_39") (pintype "bidirectional"))
    )
    (net (code "49") (name "UVCC") (class "Default")
      (node (ref "C1") (pin "2") (pinfunction "2_2") (pintype "passive"))
      (node (ref "D1") (pin "ANODE") (pinfunction "ANODE_ANODE") (pintype "bidirectional"))
      (node (ref "LED") (pin "A") (pinfunction "A_A") (pintype "passive"))
      (node (ref "U6") (pin "4") (pinfunction "VDD_4") (pintype "power_in"))
      (node (ref "X1") (pin "VBUS") (pinfunction "VBUS_VBUS") (pintype "bidirectional"))
    )
    (net (code "50") (name "VBAT") (class "Default")
      (node (ref "BAT") (pin "+") (pinfunction "+_+") (pintype "passive"))
      (node (ref "C2") (pin "2") (pinfunction "2_2") (pintype "passive"))
      (node (ref "C23") (pin "1") (pinfunction "1_1") (pintype "passive"))
      (node (ref "D1") (pin "CATHODE") (pinfunction "CATHODE_CATHODE") (pintype "bidirectional"))
      (node (ref "R9") (pin "2") (pinfunction "2_2") (pintype "passive"))
      (node (ref "SW") (pin "1") (pinfunction "1_1") (pintype "bidirectional"))
      (node (ref "SW") (pin "2") (pinfunction "2_2") (pintype "bidirectional"))
      (node (ref "U$7") (pin "4") (pinfunction "VIN_4") (pintype "bidirectional"))
      (node (ref "U10") (pin "28") (pinfunction "VBAT_28") (pintype "bidirectional"))
      (node (ref "U6") (pin "3") (pinfunction "VBAT_3") (pintype "output"))
    )
    (net (code "51") (name "WKP") (class "Default")
      (node (ref "U10") (pin "27") (pinfunction "MCU_WKUP_27") (pintype "bidirectional"))
    )
    (net (code "52") (name "unconnected-(S1-Pad2)") (class "Default")
      (node (ref "S1") (pin "2") (pinfunction "2_2") (pintype "passive"))
    )
    (net (code "53") (name "unconnected-(S1-Pad4)") (class "Default")
      (node (ref "S1") (pin "4") (pinfunction "4_4") (pintype "passive"))
    )
    (net (code "54") (name "unconnected-(S2-Pad2)") (class "Default")
      (node (ref "S2") (pin "2") (pinfunction "2_2") (pintype "passive"))
    )
    (net (code "55") (name "unconnected-(S2-Pad4)") (class "Default")
      (node (ref "S2") (pin "4") (pinfunction "4_4") (pintype "passive"))
    )
    (net (code "56") (name "unconnected-(U1-NC-Pad1)") (class "Default")
      (node (ref "U1") (pin "1") (pinfunction "NC_1") (pintype "bidirectional"))
    )
    (net (code "57") (name "unconnected-(U1-PadCD1)") (class "Default")
      (node (ref "U1") (pin "CD1") (pinfunction "CD1_CD1") (pintype "bidirectional"))
    )
    (net (code "58") (name "unconnected-(U1-PadCD2)") (class "Default")
      (node (ref "U1") (pin "CD2") (pinfunction "CD2_CD2") (pintype "bidirectional"))
    )
    (net (code "59") (name "unconnected-(U1-RSV-Pad8)") (class "Default")
      (node (ref "U1") (pin "8") (pinfunction "RSV_8") (pintype "bidirectional"))
    )
    (net (code "60") (name "unconnected-(U4-CLKOUT-Pad22)") (class "Default")
      (node (ref "U4") (pin "22") (pinfunction "CLKOUT_22") (pintype "bidirectional"))
    )
    (net (code "61") (name "unconnected-(U4-E_SCL-Pad7)") (class "Default")
      (node (ref "U4") (pin "7") (pinfunction "E_SCL_7") (pintype "bidirectional"))
    )
    (net (code "62") (name "unconnected-(U4-E_SDA-Pad6)") (class "Default")
      (node (ref "U4") (pin "6") (pinfunction "E_SDA_6") (pintype "bidirectional"))
    )
    (net (code "63") (name "unconnected-(U4-INT-Pad12)") (class "Default")
      (node (ref "U4") (pin "12") (pinfunction "INT_12") (pintype "bidirectional"))
    )
    (net (code "64") (name "unconnected-(U10-NC-Pad31)") (class "Default")
      (node (ref "U10") (pin "31") (pinfunction "NC_31") (pintype "bidirectional"))
    )
    (net (code "65") (name "unconnected-(U10-NC-Pad32)") (class "Default")
      (node (ref "U10") (pin "32") (pinfunction "NC_32") (pintype "bidirectional"))
    )
    (net (code "66") (name "unconnected-(U10-NC-Pad33)") (class "Default")
      (node (ref "U10") (pin "33") (pinfunction "NC_33") (pintype "bidirectional"))
    )
    (net (code "67") (name "unconnected-(U10-NC-Pad34)") (class "Default")
      (node (ref "U10") (pin "34") (pinfunction "NC_34") (pintype "bidirectional"))
    )
    (net (code "68") (name "unconnected-(U10-NC-Pad35)") (class "Default")
      (node (ref "U10") (pin "35") (pinfunction "NC_35") (pintype "bidirectional"))
    )
    (net (code "69") (name "unconnected-(U10-NC-Pad36)") (class "Default")
      (node (ref "U10") (pin "36") (pinfunction "NC_36") (pintype "bidirectional"))
    )
    (net (code "70") (name "~{MODE}") (class "Default")
      (node (ref "U10") (pin "53") (pinfunction "GPIO_9/PC7_53") (pintype "bidirectional"))
    )
    (net (code "71") (name "~{RST}") (class "Default")
      (node (ref "U10") (pin "26") (pinfunction "~{MCU_RST}_26") (pintype "bidirectional"))
    )
  )
)
